# T09_LockBox-Schematic_ver3.net
KiCad netlist of a schematic drawn in EAGLE
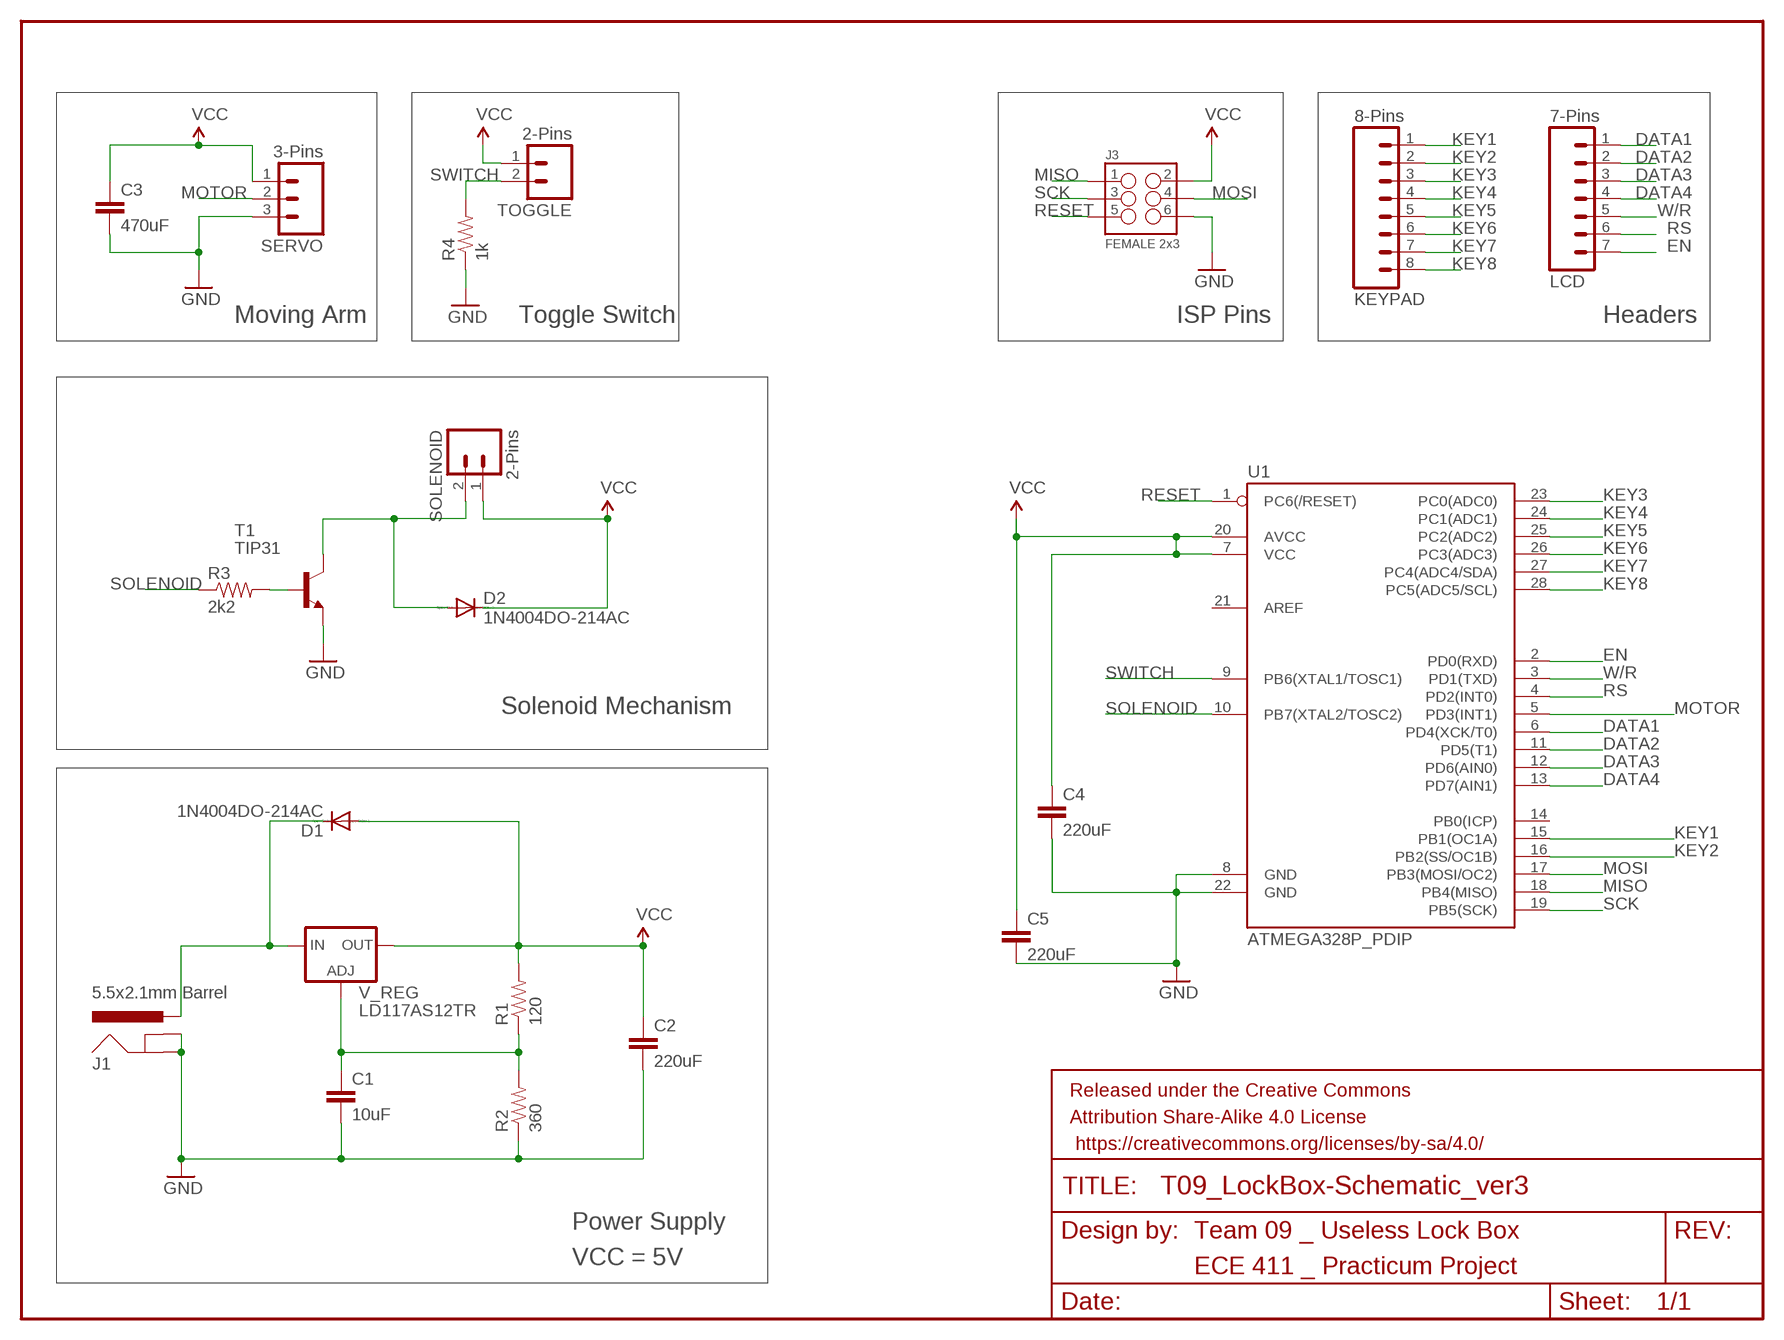
[diagram p0: schematic, sheet 1]

(export (version "E")
  (design (tool "Eeschema 10.0.6"))
  (components
    (comp (ref "C1")
      (value "10uF")
      (footprint "eagle-import:0603-CAP")
      (libsource (lib "eagle-import") (part "SparkFun-Passives_CAP0603-CAP"))
    )
    (comp (ref "C2")
      (value "220uF")
      (footprint "eagle-import:0603-CAP")
      (libsource (lib "eagle-import") (part "SparkFun-Passives_CAP0603-CAP"))
    )
    (comp (ref "C3")
      (value "470uF")
      (footprint "eagle-import:0603-CAP")
      (libsource (lib "eagle-import") (part "CAP0603-CAP"))
    )
    (comp (ref "C4")
      (value "220uF")
      (footprint "eagle-import:0603-CAP")
      (libsource (lib "eagle-import") (part "SparkFun-Passives_CAP0603-CAP"))
    )
    (comp (ref "C5")
      (value "220uF")
      (footprint "eagle-import:0603-CAP")
      (libsource (lib "eagle-import") (part "SparkFun-Passives_CAP0603-CAP"))
    )
    (comp (ref "CC_TEXT1")
      (value "CREATIVE_COMMONS")
      (footprint "eagle-import:CREATIVE_COMMONS")
      (libsource (lib "eagle-import") (part "CREATIVE_COMMONS"))
    )
    (comp (ref "D1")
      (value "1N4004DO-214AC")
      (footprint "eagle-import:DO-214AC")
      (libsource (lib "eagle-import") (part "1N4004DO-214AC"))
    )
    (comp (ref "D2")
      (value "1N4004DO-214AC")
      (footprint "eagle-import:DO-214AC")
      (libsource (lib "eagle-import") (part "1N4004DO-214AC"))
    )
    (comp (ref "FRAME1")
      (value "FRAME-LETTER")
      (footprint "eagle-import:CREATIVE_COMMONS")
      (libsource (lib "eagle-import") (part "FRAME-LETTER"))
    )
    (comp (ref "J1")
      (value "5.5x2.1mm Barrel")
      (footprint "eagle-import:POWER_JACK_SMD")
      (libsource (lib "eagle-import") (part "POWER_JACKSMD"))
    )
    (comp (ref "J3")
      (value "FEMALE 2x3")
      (footprint "eagle-import:2X3")
      (libsource (lib "eagle-import") (part "M03X2FEMALE"))
    )
    (comp (ref "KEYPAD")
      (value "8-Pins")
      (footprint "eagle-import:1X08_ROUND")
      (libsource (lib "eagle-import") (part "M08"))
    )
    (comp (ref "LCD")
      (value "7-Pins")
      (footprint "eagle-import:1X07")
      (libsource (lib "eagle-import") (part "M07"))
    )
    (comp (ref "R1")
      (value "120")
      (footprint "eagle-import:0603-RES")
      (libsource (lib "eagle-import") (part "RESISTOR0603"))
    )
    (comp (ref "R2")
      (value "360")
      (footprint "eagle-import:0603-RES")
      (libsource (lib "eagle-import") (part "RESISTOR0603"))
    )
    (comp (ref "R3")
      (value "2k2")
      (footprint "eagle-import:0603-RES")
      (libsource (lib "eagle-import") (part "RESISTOR0603"))
    )
    (comp (ref "R4")
      (value "1k")
      (footprint "eagle-import:0603-RES")
      (libsource (lib "eagle-import") (part "RESISTOR0603"))
    )
    (comp (ref "SERVO")
      (value "3-Pins")
      (footprint "eagle-import:1X03")
      (libsource (lib "eagle-import") (part "M03PTH"))
    )
    (comp (ref "SOLENOID")
      (value "2-Pins")
      (footprint "eagle-import:1X02")
      (libsource (lib "eagle-import") (part "M02PTH"))
    )
    (comp (ref "T1")
      (value "TIP31")
      (footprint "eagle-import:TO220")
      (libsource (lib "eagle-import") (part "TIP31"))
    )
    (comp (ref "TOGGLE")
      (value "2-Pins")
      (footprint "eagle-import:1X02")
      (libsource (lib "eagle-import") (part "M02PTH"))
    )
    (comp (ref "U1")
      (value "ATMEGA328P_PDIP")
      (footprint "eagle-import:DIL28-3")
      (libsource (lib "eagle-import") (part "ATMEGA328P_PDIP"))
    )
    (comp (ref "V_REG")
      (value "LD117AS12TR")
      (footprint "eagle-import:SOT223")
      (libsource (lib "eagle-import") (part "LD117A?S12TR"))
    )
  )
  (nets
    (net (code "1") (name "/DATA1") (class "Default")
      (node (ref "LCD") (pin "1") (pinfunction "1_1") (pintype "passive"))
      (node (ref "U1") (pin "6") (pinfunction "PD4(XCK/T0)_6") (pintype "bidirectional"))
    )
    (net (code "2") (name "/DATA2") (class "Default")
      (node (ref "LCD") (pin "2") (pinfunction "2_2") (pintype "passive"))
      (node (ref "U1") (pin "11") (pinfunction "PD5(T1)_11") (pintype "bidirectional"))
    )
    (net (code "3") (name "/DATA3") (class "Default")
      (node (ref "LCD") (pin "3") (pinfunction "3_3") (pintype "passive"))
      (node (ref "U1") (pin "12") (pinfunction "PD6(AIN0)_12") (pintype "bidirectional"))
    )
    (net (code "4") (name "/DATA4") (class "Default")
      (node (ref "LCD") (pin "4") (pinfunction "4_4") (pintype "passive"))
      (node (ref "U1") (pin "13") (pinfunction "PD7(AIN1)_13") (pintype "bidirectional"))
    )
    (net (code "5") (name "/EN") (class "Default")
      (node (ref "LCD") (pin "7") (pinfunction "7_7") (pintype "passive"))
      (node (ref "U1") (pin "2") (pinfunction "PD0(RXD)_2") (pintype "bidirectional"))
    )
    (net (code "6") (name "/KEY1") (class "Default")
      (node (ref "KEYPAD") (pin "1") (pinfunction "1_1") (pintype "passive"))
      (node (ref "U1") (pin "15") (pinfunction "PB1(OC1A)_15") (pintype "bidirectional"))
    )
    (net (code "7") (name "/KEY2") (class "Default")
      (node (ref "KEYPAD") (pin "2") (pinfunction "2_2") (pintype "passive"))
      (node (ref "U1") (pin "16") (pinfunction "PB2(SS/OC1B)_16") (pintype "bidirectional"))
    )
    (net (code "8") (name "/KEY3") (class "Default")
      (node (ref "KEYPAD") (pin "3") (pinfunction "3_3") (pintype "passive"))
      (node (ref "U1") (pin "23") (pinfunction "PC0(ADC0)_23") (pintype "bidirectional"))
    )
    (net (code "9") (name "/KEY4") (class "Default")
      (node (ref "KEYPAD") (pin "4") (pinfunction "4_4") (pintype "passive"))
      (node (ref "U1") (pin "24") (pinfunction "PC1(ADC1)_24") (pintype "bidirectional"))
    )
    (net (code "10") (name "/KEY5") (class "Default")
      (node (ref "KEYPAD") (pin "5") (pinfunction "5_5") (pintype "passive"))
      (node (ref "U1") (pin "25") (pinfunction "PC2(ADC2)_25") (pintype "bidirectional"))
    )
    (net (code "11") (name "/KEY6") (class "Default")
      (node (ref "KEYPAD") (pin "6") (pinfunction "6_6") (pintype "passive"))
      (node (ref "U1") (pin "26") (pinfunction "PC3(ADC3)_26") (pintype "bidirectional"))
    )
    (net (code "12") (name "/KEY7") (class "Default")
      (node (ref "KEYPAD") (pin "7") (pinfunction "7_7") (pintype "passive"))
      (node (ref "U1") (pin "27") (pinfunction "PC4(ADC4/SDA)_27") (pintype "bidirectional"))
    )
    (net (code "13") (name "/KEY8") (class "Default")
      (node (ref "KEYPAD") (pin "8") (pinfunction "8_8") (pintype "passive"))
      (node (ref "U1") (pin "28") (pinfunction "PC5(ADC5/SCL)_28") (pintype "bidirectional"))
    )
    (net (code "14") (name "/MISO") (class "Default")
      (node (ref "J3") (pin "1") (pinfunction "1_1") (pintype "bidirectional"))
      (node (ref "U1") (pin "18") (pinfunction "PB4(MISO)_18") (pintype "bidirectional"))
    )
    (net (code "15") (name "/MOSI") (class "Default")
      (node (ref "J3") (pin "4") (pinfunction "4_4") (pintype "bidirectional"))
      (node (ref "U1") (pin "17") (pinfunction "PB3(MOSI/OC2)_17") (pintype "bidirectional"))
    )
    (net (code "16") (name "/MOTOR") (class "Default")
      (node (ref "SERVO") (pin "2") (pinfunction "2_2") (pintype "passive"))
      (node (ref "U1") (pin "5") (pinfunction "PD3(INT1)_5") (pintype "bidirectional"))
    )
    (net (code "17") (name "/RESET") (class "Default")
      (node (ref "J3") (pin "5") (pinfunction "5_5") (pintype "bidirectional"))
      (node (ref "U1") (pin "1") (pinfunction "PC6(/RESET)_1") (pintype "bidirectional"))
    )
    (net (code "18") (name "/RS") (class "Default")
      (node (ref "LCD") (pin "6") (pinfunction "6_6") (pintype "passive"))
      (node (ref "U1") (pin "4") (pinfunction "PD2(INT0)_4") (pintype "bidirectional"))
    )
    (net (code "19") (name "/SCK") (class "Default")
      (node (ref "J3") (pin "3") (pinfunction "3_3") (pintype "bidirectional"))
      (node (ref "U1") (pin "19") (pinfunction "PB5(SCK)_19") (pintype "bidirectional"))
    )
    (net (code "20") (name "/SOLENOID") (class "Default")
      (node (ref "R3") (pin "1") (pinfunction "1_1") (pintype "passive"))
      (node (ref "U1") (pin "10") (pinfunction "PB7(XTAL2/TOSC2)_10") (pintype "bidirectional"))
    )
    (net (code "21") (name "/SWITCH") (class "Default")
      (node (ref "R4") (pin "2") (pinfunction "2_2") (pintype "passive"))
      (node (ref "TOGGLE") (pin "2") (pinfunction "2_2") (pintype "passive"))
      (node (ref "U1") (pin "9") (pinfunction "PB6(XTAL1/TOSC1)_9") (pintype "bidirectional"))
    )
    (net (code "22") (name "/W{slash}R") (class "Default")
      (node (ref "LCD") (pin "5") (pinfunction "5_5") (pintype "passive"))
      (node (ref "U1") (pin "3") (pinfunction "PD1(TXD)_3") (pintype "bidirectional"))
    )
    (net (code "23") (name "GND") (class "Default")
      (node (ref "C1") (pin "2") (pinfunction "2_2") (pintype "passive"))
      (node (ref "C2") (pin "2") (pinfunction "2_2") (pintype "passive"))
      (node (ref "C3") (pin "2") (pinfunction "2_2") (pintype "passive"))
      (node (ref "C4") (pin "2") (pinfunction "2_2") (pintype "passive"))
      (node (ref "C5") (pin "2") (pinfunction "2_2") (pintype "passive"))
      (node (ref "J1") (pin "GND") (pinfunction "GNDBREAK_GND") (pintype "bidirectional"))
      (node (ref "J1") (pin "P$4") (pinfunction "GND_P$4") (pintype "bidirectional"))
      (node (ref "J3") (pin "6") (pinfunction "6_6") (pintype "bidirectional"))
      (node (ref "R2") (pin "1") (pinfunction "1_1") (pintype "passive"))
      (node (ref "R4") (pin "1") (pinfunction "1_1") (pintype "passive"))
      (node (ref "SERVO") (pin "3") (pinfunction "3_3") (pintype "passive"))
      (node (ref "T1") (pin "3") (pinfunction "E_3") (pintype "passive"))
      (node (ref "U1") (pin "22") (pinfunction "GND_22") (pintype "bidirectional"))
      (node (ref "U1") (pin "8") (pinfunction "GND_8") (pintype "bidirectional"))
    )
    (net (code "24") (name "Net-(J1-PWR)") (class "Default")
      (node (ref "D1") (pin "C") (pinfunction "C_C") (pintype "passive"))
      (node (ref "J1") (pin "VIN0") (pinfunction "PWR_VIN0") (pintype "bidirectional"))
      (node (ref "V_REG") (pin "3") (pinfunction "IN_3") (pintype "input"))
    )
    (net (code "25") (name "Net-(T1-B)") (class "Default")
      (node (ref "R3") (pin "2") (pinfunction "2_2") (pintype "passive"))
      (node (ref "T1") (pin "1") (pinfunction "B_1") (pintype "passive"))
    )
    (net (code "26") (name "Net-(T1-C)") (class "Default")
      (node (ref "D2") (pin "A") (pinfunction "A_A") (pintype "passive"))
      (node (ref "SOLENOID") (pin "2") (pinfunction "2_2") (pintype "passive"))
      (node (ref "T1") (pin "2") (pinfunction "C_2") (pintype "passive"))
    )
    (net (code "27") (name "Net-(V_REG-ADJ)") (class "Default")
      (node (ref "C1") (pin "1") (pinfunction "1_1") (pintype "passive"))
      (node (ref "R1") (pin "1") (pinfunction "1_1") (pintype "passive"))
      (node (ref "R2") (pin "2") (pinfunction "2_2") (pintype "passive"))
      (node (ref "V_REG") (pin "1") (pinfunction "ADJ_1") (pintype "input"))
    )
    (net (code "28") (name "VCC") (class "Default")
      (node (ref "C2") (pin "1") (pinfunction "1_1") (pintype "passive"))
      (node (ref "C3") (pin "1") (pinfunction "1_1") (pintype "passive"))
      (node (ref "C4") (pin "1") (pinfunction "1_1") (pintype "passive"))
      (node (ref "C5") (pin "1") (pinfunction "1_1") (pintype "passive"))
      (node (ref "D1") (pin "A") (pinfunction "A_A") (pintype "passive"))
      (node (ref "D2") (pin "C") (pinfunction "C_C") (pintype "passive"))
      (node (ref "J3") (pin "2") (pinfunction "2_2") (pintype "bidirectional"))
      (node (ref "R1") (pin "2") (pinfunction "2_2") (pintype "passive"))
      (node (ref "SERVO") (pin "1") (pinfunction "1_1") (pintype "passive"))
      (node (ref "SOLENOID") (pin "1") (pinfunction "1_1") (pintype "passive"))
      (node (ref "TOGGLE") (pin "1") (pinfunction "1_1") (pintype "passive"))
      (node (ref "U1") (pin "20") (pinfunction "AVCC_20") (pintype "bidirectional"))
      (node (ref "U1") (pin "7") (pinfunction "VCC_7") (pintype "bidirectional"))
      (node (ref "V_REG") (pin "4") (pinfunction "OUT_4") (pintype "passive"))
    )
    (net (code "29") (name "unconnected-(U1-AREF-Pad21)") (class "Default")
      (node (ref "U1") (pin "21") (pinfunction "AREF_21") (pintype "bidirectional"))
    )
    (net (code "30") (name "unconnected-(U1-PB0(ICP)-Pad14)") (class "Default")
      (node (ref "U1") (pin "14") (pinfunction "PB0(ICP)_14") (pintype "bidirectional"))
    )
  )
)
